# Exemplo.net
KiCad netlist of a schematic drawn in Altium Designer
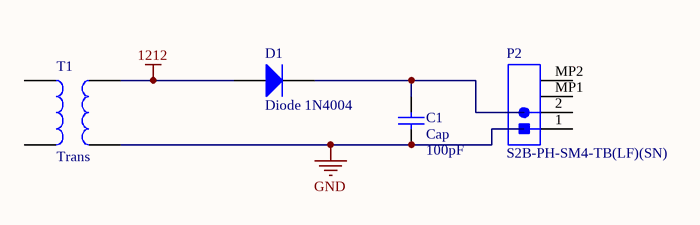
[diagram p0: Exemplo.SchDoc]

(export (version "E")
  (design (tool "Eeschema 10.0.6"))
  (components
    (comp (ref "C1")
      (value "Cap")
      (footprint "RAD-0.3")
      (description "Capacitor")
      (fields (field (name "ALTIUM_VALUE") "100pF") (field (name "PUBLISHER") "Altium Limited"))
      (libsource (lib "Miscellaneous Devices") (part "Cap"))
    )
    (comp (ref "D1")
      (value "Diode 1N4004")
      (footprint "DO-41")
      (description "1 Amp General Purpose Rectifier")
      (fields (field (name "PUBLISHER") "Altium Limited"))
      (libsource (lib "Miscellaneous Devices") (part "Diode 1N4004"))
    )
    (comp (ref "P2")
      (value "S2B-PH-SM4-TB(LF)(SN)")
      (footprint "JST- S2B-PH-SM4-TB(LF)(SN)-2_V")
      (description "Male Header, Pitch 2 mm, 1 x 2 Position, Height 5.5 mm, -25 to 85 degC, RoHS, Tape and Reel")
      (fields (field (name "MANUFACTURER") "JST"))
      (libsource (lib "IME") (part "CN-1P-2M-R2"))
    )
    (comp (ref "T1")
      (value "Trans")
      (footprint "TRANS")
      (description "Transformer")
      (fields (field (name "PUBLISHER") "Altium Limited"))
      (libsource (lib "Miscellaneous Devices") (part "Trans"))
    )
  )
  (nets
    (net (code "1") (name "1212") (class "Default")
      (node (ref "D1") (pin "1") (pinfunction "A_1") (pintype "passive"))
      (node (ref "T1") (pin "3") (pinfunction "3_3") (pintype "passive"))
    )
    (net (code "2") (name "GND") (class "Default")
      (node (ref "C1") (pin "1") (pinfunction "1_1") (pintype "passive"))
      (node (ref "T1") (pin "4") (pinfunction "4_4") (pintype "passive"))
    )
    (net (code "3") (name "Net-(D1-K)") (class "Default")
      (node (ref "C1") (pin "2") (pinfunction "2_2") (pintype "passive"))
      (node (ref "D1") (pin "2") (pinfunction "K_2") (pintype "passive"))
    )
    (net (code "4") (name "unconnected-(P2-Pad1)") (class "Default")
      (node (ref "P2") (pin "1") (pinfunction "1_1") (pintype "passive"))
    )
    (net (code "5") (name "unconnected-(P2-Pad2)") (class "Default")
      (node (ref "P2") (pin "2") (pinfunction "2_2") (pintype "passive"))
    )
    (net (code "6") (name "unconnected-(P2-PadMP1)") (class "Default")
      (node (ref "P2") (pin "MP1") (pinfunction "MP1_MP1") (pintype "passive"))
    )
    (net (code "7") (name "unconnected-(P2-PadMP2)") (class "Default")
      (node (ref "P2") (pin "MP2") (pinfunction "MP2_MP2") (pintype "passive"))
    )
    (net (code "8") (name "unconnected-(T1-Pad1)") (class "Default")
      (node (ref "T1") (pin "1") (pinfunction "1_1") (pintype "passive"))
    )
    (net (code "9") (name "unconnected-(T1-Pad2)") (class "Default")
      (node (ref "T1") (pin "2") (pinfunction "2_2") (pintype "passive"))
    )
  )
)
